# SCH002.net
KiCad netlist of a schematic drawn in Altium Designer
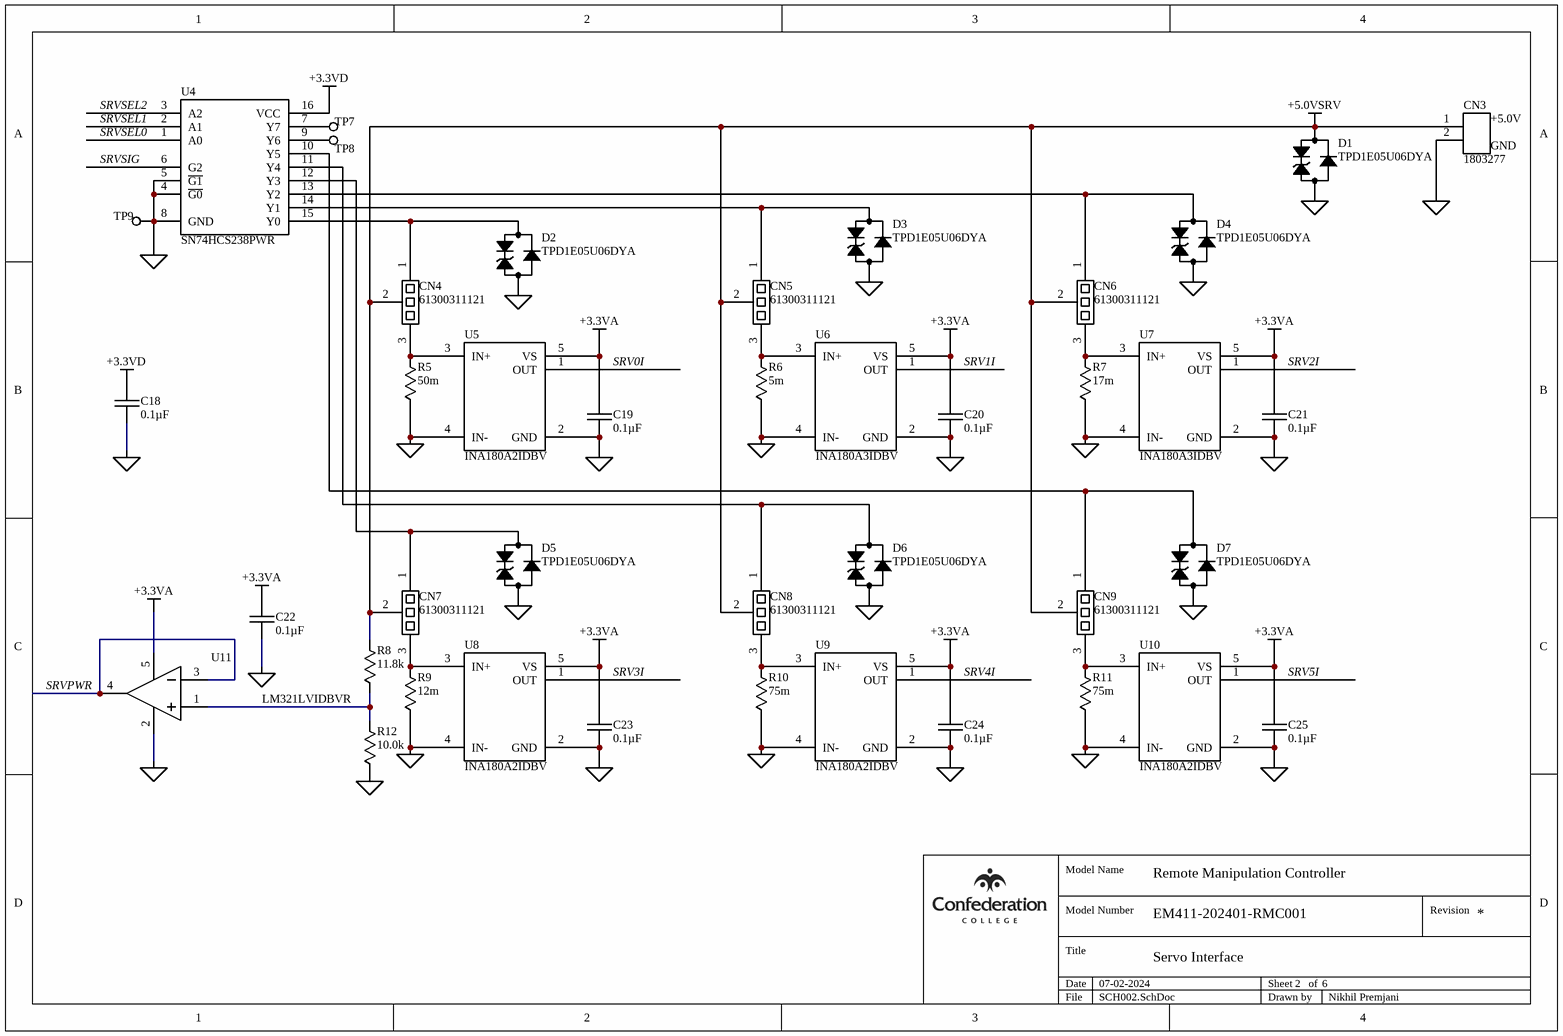
[diagram p0: SCH002.SchDoc]

(export (version "E")
  (design (tool "Eeschema 10.0.6"))
  (components
    (comp (ref "C18")
      (value "0.1µF")
      (footprint "CAPC2012X14N")
      (description "0.1µF/50V/±10% X7R Ceramic Chip Capacitor")
      (fields (field (name "MANUFACTURER") "Taiyo Yuden") (field (name "PARTNUMBER") "UMK212B7104KGHT"))
      (libsource (lib "EM411-202401-RMC001-000-20240206") (part "UMK212B7104KGHT"))
    )
    (comp (ref "C19")
      (value "0.1µF")
      (footprint "CAPC2012X14N")
      (description "0.1µF/50V/±10% X7R Ceramic Chip Capacitor")
      (fields (field (name "MANUFACTURER") "Taiyo Yuden") (field (name "PARTNUMBER") "UMK212B7104KGHT"))
      (libsource (lib "EM411-202401-RMC001-001") (part "UMK212B7104KGHT"))
    )
    (comp (ref "C20")
      (value "0.1µF")
      (footprint "CAPC2012X14N")
      (description "0.1µF/50V/±10% X7R Ceramic Chip Capacitor")
      (fields (field (name "MANUFACTURER") "Taiyo Yuden") (field (name "PARTNUMBER") "UMK212B7104KGHT"))
      (libsource (lib "EM411-202401-RMC001-001") (part "UMK212B7104KGHT"))
    )
    (comp (ref "C21")
      (value "0.1µF")
      (footprint "CAPC2012X14N")
      (description "0.1µF/50V/±10% X7R Ceramic Chip Capacitor")
      (fields (field (name "MANUFACTURER") "Taiyo Yuden") (field (name "PARTNUMBER") "UMK212B7104KGHT"))
      (libsource (lib "EM411-202401-RMC001-001") (part "UMK212B7104KGHT"))
    )
    (comp (ref "C22")
      (value "0.1µF")
      (footprint "CAPC2012X14N")
      (description "0.1µF/50V/±10% X7R Ceramic Chip Capacitor")
      (fields (field (name "MANUFACTURER") "Taiyo Yuden") (field (name "PARTNUMBER") "UMK212B7104KGHT"))
      (libsource (lib "EM411-202401-RMC001-000-20240206") (part "UMK212B7104KGHT"))
    )
    (comp (ref "C23")
      (value "0.1µF")
      (footprint "CAPC2012X14N")
      (description "0.1µF/50V/±10% X7R Ceramic Chip Capacitor")
      (fields (field (name "MANUFACTURER") "Taiyo Yuden") (field (name "PARTNUMBER") "UMK212B7104KGHT"))
      (libsource (lib "EM411-202401-RMC001-001") (part "UMK212B7104KGHT"))
    )
    (comp (ref "C24")
      (value "0.1µF")
      (footprint "CAPC2012X14N")
      (description "0.1µF/50V/±10% X7R Ceramic Chip Capacitor")
      (fields (field (name "MANUFACTURER") "Taiyo Yuden") (field (name "PARTNUMBER") "UMK212B7104KGHT"))
      (libsource (lib "EM411-202401-RMC001-001") (part "UMK212B7104KGHT"))
    )
    (comp (ref "C25")
      (value "0.1µF")
      (footprint "CAPC2012X14N")
      (description "0.1µF/50V/±10% X7R Ceramic Chip Capacitor")
      (fields (field (name "MANUFACTURER") "Taiyo Yuden") (field (name "PARTNUMBER") "UMK212B7104KGHT"))
      (libsource (lib "EM411-202401-RMC001-001") (part "UMK212B7104KGHT"))
    )
    (comp (ref "CN3")
      (value "1803277")
      (footprint "PHOENIX_1803277")
      (description "MC 1,5/2G-3,81 Pluggable Terminal Block 2 Pos 3.81mm pitch Through Hole Header")
      (fields (field (name "MANUFACTURER") "Phoenix Contact"))
      (libsource (lib "EM411-202401-RMC001-000-20240213-T10") (part "1803277"))
    )
    (comp (ref "CN4")
      (value "61300311121")
      (footprint "WURTH_61300311121")
      (description "Connector Header Through Hole 3 position 0.100\" (2.54mm)")
      (fields (field (name "MANUFACTURER") "Wurth Elektronik"))
      (libsource (lib "EM411-202401-RMC001-000-20240213-T10") (part "61300311121"))
    )
    (comp (ref "CN5")
      (value "61300311121")
      (footprint "WURTH_61300311121")
      (description "Connector Header Through Hole 3 position 0.100\" (2.54mm)")
      (fields (field (name "MANUFACTURER") "Wurth Elektronik"))
      (libsource (lib "EM411-202401-RMC001-000-20240213-T10") (part "61300311121"))
    )
    (comp (ref "CN6")
      (value "61300311121")
      (footprint "WURTH_61300311121")
      (description "Connector Header Through Hole 3 position 0.100\" (2.54mm)")
      (fields (field (name "MANUFACTURER") "Wurth Elektronik"))
      (libsource (lib "EM411-202401-RMC001-000-20240213-T10") (part "61300311121"))
    )
    (comp (ref "CN7")
      (value "61300311121")
      (footprint "WURTH_61300311121")
      (description "Connector Header Through Hole 3 position 0.100\" (2.54mm)")
      (fields (field (name "MANUFACTURER") "Wurth Elektronik"))
      (libsource (lib "EM411-202401-RMC001-000-20240213-T10") (part "61300311121"))
    )
    (comp (ref "CN8")
      (value "61300311121")
      (footprint "WURTH_61300311121")
      (description "Connector Header Through Hole 3 position 0.100\" (2.54mm)")
      (fields (field (name "MANUFACTURER") "Wurth Elektronik"))
      (libsource (lib "EM411-202401-RMC001-000-20240213-T10") (part "61300311121"))
    )
    (comp (ref "CN9")
      (value "61300311121")
      (footprint "WURTH_61300311121")
      (description "Connector Header Through Hole 3 position 0.100\" (2.54mm)")
      (fields (field (name "MANUFACTURER") "Wurth Elektronik"))
      (libsource (lib "EM411-202401-RMC001-000-20240213-T10") (part "61300311121"))
    )
    (comp (ref "D1")
      (value "TPD1E05U06DYA")
      (footprint "SODFL160X77-2N")
      (description "Single-Channel ESD Protection Diode")
      (fields (field (name "MANUFACTURER") "Texas Instruments"))
      (libsource (lib "EM411-202401-RMC001-001") (part "TPD1E05U06DYA"))
    )
    (comp (ref "D2")
      (value "TPD1E05U06DYA")
      (footprint "SODFL160X77-2N")
      (description "Single-Channel ESD Protection Diode")
      (fields (field (name "MANUFACTURER") "Texas Instruments"))
      (libsource (lib "EM411-202401-RMC001-001") (part "TPD1E05U06DYA"))
    )
    (comp (ref "D3")
      (value "TPD1E05U06DYA")
      (footprint "SODFL160X77-2N")
      (description "Single-Channel ESD Protection Diode")
      (fields (field (name "MANUFACTURER") "Texas Instruments"))
      (libsource (lib "EM411-202401-RMC001-001") (part "TPD1E05U06DYA"))
    )
    (comp (ref "D4")
      (value "TPD1E05U06DYA")
      (footprint "SODFL160X77-2N")
      (description "Single-Channel ESD Protection Diode")
      (fields (field (name "MANUFACTURER") "Texas Instruments"))
      (libsource (lib "EM411-202401-RMC001-001") (part "TPD1E05U06DYA"))
    )
    (comp (ref "D5")
      (value "TPD1E05U06DYA")
      (footprint "SODFL160X77-2N")
      (description "Single-Channel ESD Protection Diode")
      (fields (field (name "MANUFACTURER") "Texas Instruments"))
      (libsource (lib "EM411-202401-RMC001-001") (part "TPD1E05U06DYA"))
    )
    (comp (ref "D6")
      (value "TPD1E05U06DYA")
      (footprint "SODFL160X77-2N")
      (description "Single-Channel ESD Protection Diode")
      (fields (field (name "MANUFACTURER") "Texas Instruments"))
      (libsource (lib "EM411-202401-RMC001-001") (part "TPD1E05U06DYA"))
    )
    (comp (ref "D7")
      (value "TPD1E05U06DYA")
      (footprint "SODFL160X77-2N")
      (description "Single-Channel ESD Protection Diode")
      (fields (field (name "MANUFACTURER") "Texas Instruments"))
      (libsource (lib "EM411-202401-RMC001-001") (part "TPD1E05U06DYA"))
    )
    (comp (ref "R5")
      (value "50m")
      (footprint "RESC2012X08N")
      (description "50m, 1%, 0.5W Thick Film Chip Resistor")
      (fields (field (name "MANUFACTURER") "Panasonic") (field (name "PARTNUMBER") "ERJ-6BWFR050V"))
      (libsource (lib "EM411-202401-RMC001-000-20240213-T10") (part "ERJ-6BWFR050V"))
    )
    (comp (ref "R6")
      (value "5m")
      (footprint "RESC2012X08N")
      (description "5m, 1%, 0.5W Thick Film Chip Resistor")
      (fields (field (name "MANUFACTURER") "Bourns") (field (name "PARTNUMBER") "CRF0805-FZ-R005ELF"))
      (libsource (lib "EM411-202401-RMC001-000-20240213-T10") (part "CRF0805-FZ-R005ELF"))
    )
    (comp (ref "R7")
      (value "17m")
      (footprint "RESC2013X05N")
      (description "17m, 1%, 0.5W Thick Film Chip Resistor")
      (fields (field (name "MANUFACTURER") "Vishay Dale") (field (name "PARTNUMBER") "WSLP0805R0170FEB"))
      (libsource (lib "EM411-202401-RMC001-000-20240213-T10") (part "WSLP0805R0170FEB"))
    )
    (comp (ref "R8")
      (value "11.8k")
      (footprint "RESC2012X06N")
      (description "11.8k, 1%, 0.125W Thick Film Chip Resistor")
      (fields (field (name "MANUFACTURER") "Bourns") (field (name "PARTNUMBER") "CR0805-FX-1182ELF"))
      (libsource (lib "EM411-202401-RMC001-000-20240213-T10") (part "CR0805-FX-1182ELF"))
    )
    (comp (ref "R9")
      (value "12m")
      (footprint "RESC2012X08N")
      (description "12m, 1%, 0.5W Thick Film Chip Resistor")
      (fields (field (name "MANUFACTURER") "Panasonic") (field (name "PARTNUMBER") "ERJ-6BWFR012V"))
      (libsource (lib "EM411-202401-RMC001-000-20240213-T10") (part "ERJ-6BWFR012V"))
    )
    (comp (ref "R10")
      (value "75m")
      (footprint "RESC2012X08N")
      (description "75m, 1%, 0.5W Thick Film Chip Resistor")
      (fields (field (name "MANUFACTURER") "Panasonic") (field (name "PARTNUMBER") "ERJ-6BWFR075V"))
      (libsource (lib "EM411-202401-RMC001-000-20240213-T10") (part "ERJ-6BWFR075V"))
    )
    (comp (ref "R11")
      (value "75m")
      (footprint "RESC2012X08N")
      (description "75m, 1%, 0.5W Thick Film Chip Resistor")
      (fields (field (name "MANUFACTURER") "Panasonic") (field (name "PARTNUMBER") "ERJ-6BWFR075V"))
      (libsource (lib "EM411-202401-RMC001-000-20240213-T10") (part "ERJ-6BWFR075V"))
    )
    (comp (ref "R12")
      (value "10.0k")
      (footprint "RESC2012X06N")
      (description "10.0k, 1%, 0.125W Thick Film Chip Resistor")
      (fields (field (name "MANUFACTURER") "Bourns") (field (name "PARTNUMBER") "CR0805-FX-1002ELF"))
      (libsource (lib "EM411-202401-RMC001-000-20240206") (part "CR0805-FX-1002ELF"))
    )
    (comp (ref "TP7")
      (value "Test Point")
      (footprint "TP100")
      (description "Test Point, Surface Mount, 3 mm")
      (fields (field (name "MANUFACTURER") "Confederation College"))
      (libsource (lib "EM411-202401-RMC001-000-20240213-T10") (part "TP3"))
    )
    (comp (ref "TP8")
      (value "Test Point")
      (footprint "TP100")
      (description "Test Point, Surface Mount, 3 mm")
      (fields (field (name "MANUFACTURER") "Confederation College"))
      (libsource (lib "EM411-202401-RMC001-000-20240213-T10") (part "TP3"))
    )
    (comp (ref "TP9")
      (value "Test Point")
      (footprint "TP100")
      (description "Test Point, Surface Mount, 3 mm")
      (fields (field (name "MANUFACTURER") "Confederation College"))
      (libsource (lib "EM411-202401-RMC001-000-20240213-T10") (part "TP3"))
    )
    (comp (ref "U4")
      (value "SN74HCS238PWR")
      (footprint "TSOP65P640X120-16N")
      (description "3-to 8-Line Decoder/Demultiplexer with Schmitt-Trigger Inputs")
      (fields (field (name "MANUFACTURER") "Texas Instruments"))
      (libsource (lib "EM411-202401-RMC001-001") (part "SN74HCS238PWR"))
    )
    (comp (ref "U5")
      (value "INA180A2IDBV")
      (footprint "SOT95P280X145-5N")
      (description "Voltage Output, Current-Sense Amplifiers, Gain 50")
      (fields (field (name "MANUFACTURER") "Texas Instruments"))
      (libsource (lib "EM411-202401-RMC001-000-20240213-T10") (part "INA180A2IDBV"))
    )
    (comp (ref "U6")
      (value "INA180A3IDBV")
      (footprint "SOT95P280X145-5N")
      (description "Voltage Output, Current-Sense Amplifiers, Gain 100")
      (fields (field (name "MANUFACTURER") "Texas Instruments"))
      (libsource (lib "EM411-202401-RMC001-000-20240213-T10") (part "INA180A3IDBV"))
    )
    (comp (ref "U7")
      (value "INA180A3IDBV")
      (footprint "SOT95P280X145-5N")
      (description "Voltage Output, Current-Sense Amplifiers, Gain 100")
      (fields (field (name "MANUFACTURER") "Texas Instruments"))
      (libsource (lib "EM411-202401-RMC001-000-20240213-T10") (part "INA180A3IDBV"))
    )
    (comp (ref "U8")
      (value "INA180A2IDBV")
      (footprint "SOT95P280X145-5N")
      (description "Voltage Output, Current-Sense Amplifiers, Gain 50")
      (fields (field (name "MANUFACTURER") "Texas Instruments"))
      (libsource (lib "EM411-202401-RMC001-000-20240213-T10") (part "INA180A2IDBV"))
    )
    (comp (ref "U9")
      (value "INA180A2IDBV")
      (footprint "SOT95P280X145-5N")
      (description "Voltage Output, Current-Sense Amplifiers, Gain 50")
      (fields (field (name "MANUFACTURER") "Texas Instruments"))
      (libsource (lib "EM411-202401-RMC001-000-20240213-T10") (part "INA180A2IDBV"))
    )
    (comp (ref "U10")
      (value "INA180A2IDBV")
      (footprint "SOT95P280X145-5N")
      (description "Voltage Output, Current-Sense Amplifiers, Gain 50")
      (fields (field (name "MANUFACTURER") "Texas Instruments"))
      (libsource (lib "EM411-202401-RMC001-000-20240213-T10") (part "INA180A2IDBV"))
    )
    (comp (ref "U11")
      (value "LM321LVIDBVR")
      (footprint "SOT95P280X145-5N")
      (description "Industry Standard, Low Voltage Operational Amplifier")
      (fields (field (name "MANUFACTURER") "Texas Instruments"))
      (libsource (lib "EM411-202401-RMC001-000-20240213-T10") (part "LM321LVIDBVR"))
    )
  )
  (nets
    (net (code "1") (name "+3.3VA") (class "Default")
      (node (ref "C19") (pin "1") (pinfunction "1_1") (pintype "passive"))
      (node (ref "C20") (pin "1") (pinfunction "1_1") (pintype "passive"))
      (node (ref "C21") (pin "1") (pinfunction "1_1") (pintype "passive"))
      (node (ref "C22") (pin "1") (pinfunction "1_1") (pintype "passive"))
      (node (ref "C23") (pin "1") (pinfunction "1_1") (pintype "passive"))
      (node (ref "C24") (pin "1") (pinfunction "1_1") (pintype "passive"))
      (node (ref "C25") (pin "1") (pinfunction "1_1") (pintype "passive"))
      (node (ref "U10") (pin "5") (pinfunction "VS_5") (pintype "passive"))
      (node (ref "U11") (pin "5") (pinfunction "V+_5") (pintype "power_in"))
      (node (ref "U5") (pin "5") (pinfunction "VS_5") (pintype "passive"))
      (node (ref "U6") (pin "5") (pinfunction "VS_5") (pintype "passive"))
      (node (ref "U7") (pin "5") (pinfunction "VS_5") (pintype "passive"))
      (node (ref "U8") (pin "5") (pinfunction "VS_5") (pintype "passive"))
      (node (ref "U9") (pin "5") (pinfunction "VS_5") (pintype "passive"))
    )
    (net (code "2") (name "+3.3VD") (class "Default")
      (node (ref "C18") (pin "1") (pinfunction "1_1") (pintype "passive"))
      (node (ref "U4") (pin "16") (pinfunction "VCC_16") (pintype "passive"))
    )
    (net (code "3") (name "+5.0VSRV") (class "Default")
      (node (ref "CN3") (pin "1") (pinfunction "1_1") (pintype "passive"))
      (node (ref "CN4") (pin "2") (pinfunction "2_2") (pintype "passive"))
      (node (ref "CN5") (pin "2") (pinfunction "2_2") (pintype "passive"))
      (node (ref "CN6") (pin "2") (pinfunction "2_2") (pintype "passive"))
      (node (ref "CN7") (pin "2") (pinfunction "2_2") (pintype "passive"))
      (node (ref "CN8") (pin "2") (pinfunction "2_2") (pintype "passive"))
      (node (ref "CN9") (pin "2") (pinfunction "2_2") (pintype "passive"))
      (node (ref "D1") (pin "K") (pinfunction "K_K") (pintype "passive"))
      (node (ref "R8") (pin "2") (pinfunction "2_2") (pintype "passive"))
    )
    (net (code "4") (name "/SRV0I") (class "Default")
      (node (ref "U5") (pin "1") (pinfunction "OUT_1") (pintype "passive"))
    )
    (net (code "5") (name "/SRV1I") (class "Default")
      (node (ref "U6") (pin "1") (pinfunction "OUT_1") (pintype "passive"))
    )
    (net (code "6") (name "/SRV2I") (class "Default")
      (node (ref "U7") (pin "1") (pinfunction "OUT_1") (pintype "passive"))
    )
    (net (code "7") (name "/SRV3I") (class "Default")
      (node (ref "U8") (pin "1") (pinfunction "OUT_1") (pintype "passive"))
    )
    (net (code "8") (name "/SRV4I") (class "Default")
      (node (ref "U9") (pin "1") (pinfunction "OUT_1") (pintype "passive"))
    )
    (net (code "9") (name "/SRV5I") (class "Default")
      (node (ref "U10") (pin "1") (pinfunction "OUT_1") (pintype "passive"))
    )
    (net (code "10") (name "/SRVPWR") (class "Default")
      (node (ref "U11") (pin "3") (pinfunction "IN-_3") (pintype "passive"))
      (node (ref "U11") (pin "4") (pinfunction "OUT_4") (pintype "passive"))
    )
    (net (code "11") (name "/SRVSEL0") (class "Default")
      (node (ref "U4") (pin "1") (pinfunction "A0_1") (pintype "passive"))
    )
    (net (code "12") (name "/SRVSEL1") (class "Default")
      (node (ref "U4") (pin "2") (pinfunction "A1_2") (pintype "passive"))
    )
    (net (code "13") (name "/SRVSEL2") (class "Default")
      (node (ref "U4") (pin "3") (pinfunction "A2_3") (pintype "passive"))
    )
    (net (code "14") (name "/SRVSIG") (class "Default")
      (node (ref "U4") (pin "6") (pinfunction "G2_6") (pintype "passive"))
    )
    (net (code "15") (name "GND") (class "Default")
      (node (ref "C18") (pin "2") (pinfunction "2_2") (pintype "passive"))
      (node (ref "C19") (pin "2") (pinfunction "2_2") (pintype "passive"))
      (node (ref "C20") (pin "2") (pinfunction "2_2") (pintype "passive"))
      (node (ref "C21") (pin "2") (pinfunction "2_2") (pintype "passive"))
      (node (ref "C22") (pin "2") (pinfunction "2_2") (pintype "passive"))
      (node (ref "C23") (pin "2") (pinfunction "2_2") (pintype "passive"))
      (node (ref "C24") (pin "2") (pinfunction "2_2") (pintype "passive"))
      (node (ref "C25") (pin "2") (pinfunction "2_2") (pintype "passive"))
      (node (ref "CN3") (pin "2") (pinfunction "2_2") (pintype "passive"))
      (node (ref "D1") (pin "A") (pinfunction "A_A") (pintype "passive"))
      (node (ref "D2") (pin "A") (pinfunction "A_A") (pintype "passive"))
      (node (ref "D3") (pin "A") (pinfunction "A_A") (pintype "passive"))
      (node (ref "D4") (pin "A") (pinfunction "A_A") (pintype "passive"))
      (node (ref "D5") (pin "A") (pinfunction "A_A") (pintype "passive"))
      (node (ref "D6") (pin "A") (pinfunction "A_A") (pintype "passive"))
      (node (ref "D7") (pin "A") (pinfunction "A_A") (pintype "passive"))
      (node (ref "R10") (pin "1") (pinfunction "1_1") (pintype "passive"))
      (node (ref "R11") (pin "1") (pinfunction "1_1") (pintype "passive"))
      (node (ref "R12") (pin "1") (pinfunction "1_1") (pintype "passive"))
      (node (ref "R5") (pin "1") (pinfunction "1_1") (pintype "passive"))
      (node (ref "R6") (pin "1") (pinfunction "1_1") (pintype "passive"))
      (node (ref "R7") (pin "1") (pinfunction "1_1") (pintype "passive"))
      (node (ref "R9") (pin "1") (pinfunction "1_1") (pintype "passive"))
      (node (ref "TP9") (pin "1") (pinfunction "1_1") (pintype "passive"))
      (node (ref "U10") (pin "2") (pinfunction "GND_2") (pintype "passive"))
      (node (ref "U10") (pin "4") (pinfunction "IN-_4") (pintype "passive"))
      (node (ref "U11") (pin "2") (pinfunction "V-_2") (pintype "power_in"))
      (node (ref "U4") (pin "4") (pinfunction "~{G0}_4") (pintype "passive"))
      (node (ref "U4") (pin "5") (pinfunction "~{G1}_5") (pintype "passive"))
      (node (ref "U4") (pin "8") (pinfunction "GND_8") (pintype "passive"))
      (node (ref "U5") (pin "2") (pinfunction "GND_2") (pintype "passive"))
      (node (ref "U5") (pin "4") (pinfunction "IN-_4") (pintype "passive"))
      (node (ref "U6") (pin "2") (pinfunction "GND_2") (pintype "passive"))
      (node (ref "U6") (pin "4") (pinfunction "IN-_4") (pintype "passive"))
      (node (ref "U7") (pin "2") (pinfunction "GND_2") (pintype "passive"))
      (node (ref "U7") (pin "4") (pinfunction "IN-_4") (pintype "passive"))
      (node (ref "U8") (pin "2") (pinfunction "GND_2") (pintype "passive"))
      (node (ref "U8") (pin "4") (pinfunction "IN-_4") (pintype "passive"))
      (node (ref "U9") (pin "2") (pinfunction "GND_2") (pintype "passive"))
      (node (ref "U9") (pin "4") (pinfunction "IN-_4") (pintype "passive"))
    )
    (net (code "16") (name "Net-(U4-Y0)") (class "Default")
      (node (ref "CN4") (pin "1") (pinfunction "1_1") (pintype "passive"))
      (node (ref "D2") (pin "K") (pinfunction "K_K") (pintype "passive"))
      (node (ref "U4") (pin "15") (pinfunction "Y0_15") (pintype "passive"))
    )
    (net (code "17") (name "Net-(U4-Y1)") (class "Default")
      (node (ref "CN5") (pin "1") (pinfunction "1_1") (pintype "passive"))
      (node (ref "D3") (pin "K") (pinfunction "K_K") (pintype "passive"))
      (node (ref "U4") (pin "14") (pinfunction "Y1_14") (pintype "passive"))
    )
    (net (code "18") (name "Net-(U4-Y2)") (class "Default")
      (node (ref "CN6") (pin "1") (pinfunction "1_1") (pintype "passive"))
      (node (ref "D4") (pin "K") (pinfunction "K_K") (pintype "passive"))
      (node (ref "U4") (pin "13") (pinfunction "Y2_13") (pintype "passive"))
    )
    (net (code "19") (name "Net-(U4-Y3)") (class "Default")
      (node (ref "CN7") (pin "1") (pinfunction "1_1") (pintype "passive"))
      (node (ref "D5") (pin "K") (pinfunction "K_K") (pintype "passive"))
      (node (ref "U4") (pin "12") (pinfunction "Y3_12") (pintype "passive"))
    )
    (net (code "20") (name "Net-(U4-Y4)") (class "Default")
      (node (ref "CN8") (pin "1") (pinfunction "1_1") (pintype "passive"))
      (node (ref "D6") (pin "K") (pinfunction "K_K") (pintype "passive"))
      (node (ref "U4") (pin "11") (pinfunction "Y4_11") (pintype "passive"))
    )
    (net (code "21") (name "Net-(U4-Y5)") (class "Default")
      (node (ref "CN9") (pin "1") (pinfunction "1_1") (pintype "passive"))
      (node (ref "D7") (pin "K") (pinfunction "K_K") (pintype "passive"))
      (node (ref "U4") (pin "10") (pinfunction "Y5_10") (pintype "passive"))
    )
    (net (code "22") (name "Net-(U4-Y6)") (class "Default")
      (node (ref "TP8") (pin "1") (pinfunction "1_1") (pintype "passive"))
      (node (ref "U4") (pin "9") (pinfunction "Y6_9") (pintype "passive"))
    )
    (net (code "23") (name "Net-(U4-Y7)") (class "Default")
      (node (ref "TP7") (pin "1") (pinfunction "1_1") (pintype "passive"))
      (node (ref "U4") (pin "7") (pinfunction "Y7_7") (pintype "passive"))
    )
    (net (code "24") (name "Net-(U5-IN+)") (class "Default")
      (node (ref "CN4") (pin "3") (pinfunction "3_3") (pintype "passive"))
      (node (ref "R5") (pin "2") (pinfunction "2_2") (pintype "passive"))
      (node (ref "U5") (pin "3") (pinfunction "IN+_3") (pintype "passive"))
    )
    (net (code "25") (name "Net-(U6-IN+)") (class "Default")
      (node (ref "CN5") (pin "3") (pinfunction "3_3") (pintype "passive"))
      (node (ref "R6") (pin "2") (pinfunction "2_2") (pintype "passive"))
      (node (ref "U6") (pin "3") (pinfunction "IN+_3") (pintype "passive"))
    )
    (net (code "26") (name "Net-(U7-IN+)") (class "Default")
      (node (ref "CN6") (pin "3") (pinfunction "3_3") (pintype "passive"))
      (node (ref "R7") (pin "2") (pinfunction "2_2") (pintype "passive"))
      (node (ref "U7") (pin "3") (pinfunction "IN+_3") (pintype "passive"))
    )
    (net (code "27") (name "Net-(U8-IN+)") (class "Default")
      (node (ref "CN7") (pin "3") (pinfunction "3_3") (pintype "passive"))
      (node (ref "R9") (pin "2") (pinfunction "2_2") (pintype "passive"))
      (node (ref "U8") (pin "3") (pinfunction "IN+_3") (pintype "passive"))
    )
    (net (code "28") (name "Net-(U9-IN+)") (class "Default")
      (node (ref "CN8") (pin "3") (pinfunction "3_3") (pintype "passive"))
      (node (ref "R10") (pin "2") (pinfunction "2_2") (pintype "passive"))
      (node (ref "U9") (pin "3") (pinfunction "IN+_3") (pintype "passive"))
    )
    (net (code "29") (name "Net-(U10-IN+)") (class "Default")
      (node (ref "CN9") (pin "3") (pinfunction "3_3") (pintype "passive"))
      (node (ref "R11") (pin "2") (pinfunction "2_2") (pintype "passive"))
      (node (ref "U10") (pin "3") (pinfunction "IN+_3") (pintype "passive"))
    )
    (net (code "30") (name "Net-(U11-IN+)") (class "Default")
      (node (ref "R12") (pin "2") (pinfunction "2_2") (pintype "passive"))
      (node (ref "R8") (pin "1") (pinfunction "1_1") (pintype "passive"))
      (node (ref "U11") (pin "1") (pinfunction "IN+_1") (pintype "passive"))
    )
  )
)
